# 43-OVER_VOLTAGE_PROTECTION_CKT.net
KiCad netlist of a schematic drawn in Altium Designer
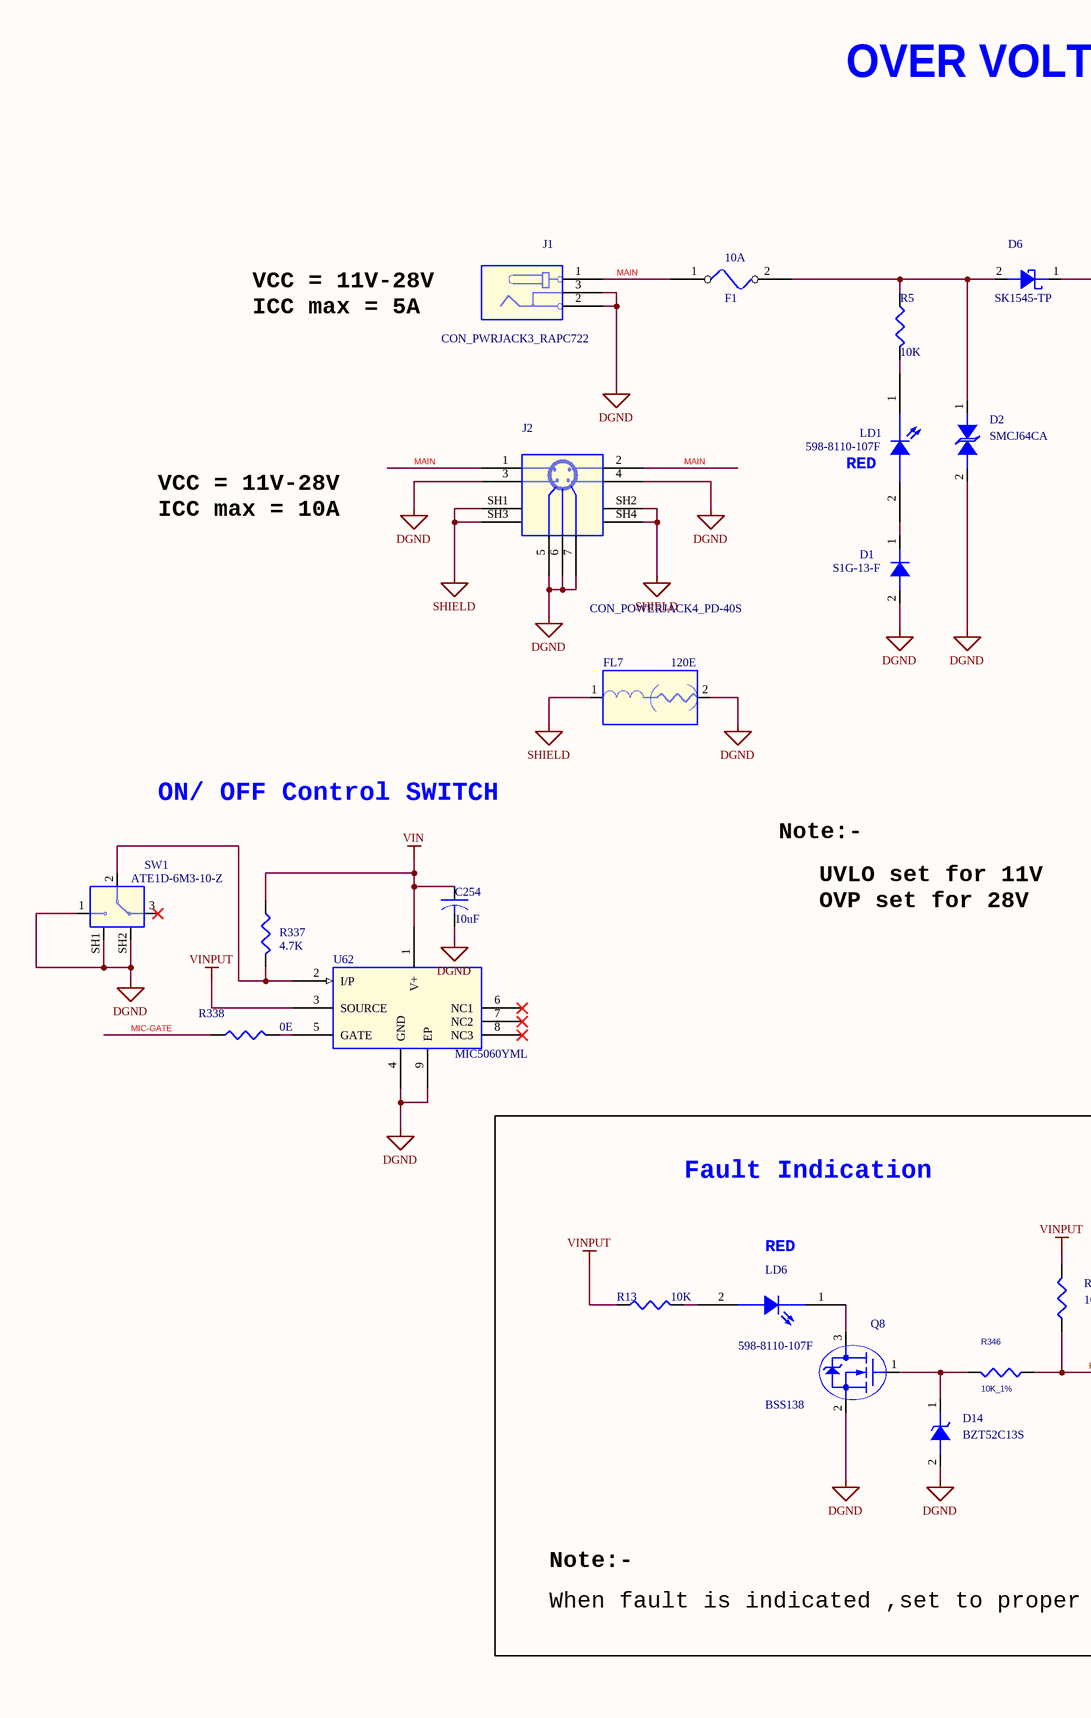
[diagram p0: 43-OVER VOLTAGE PROTECTION CKT.SchDoc, left]
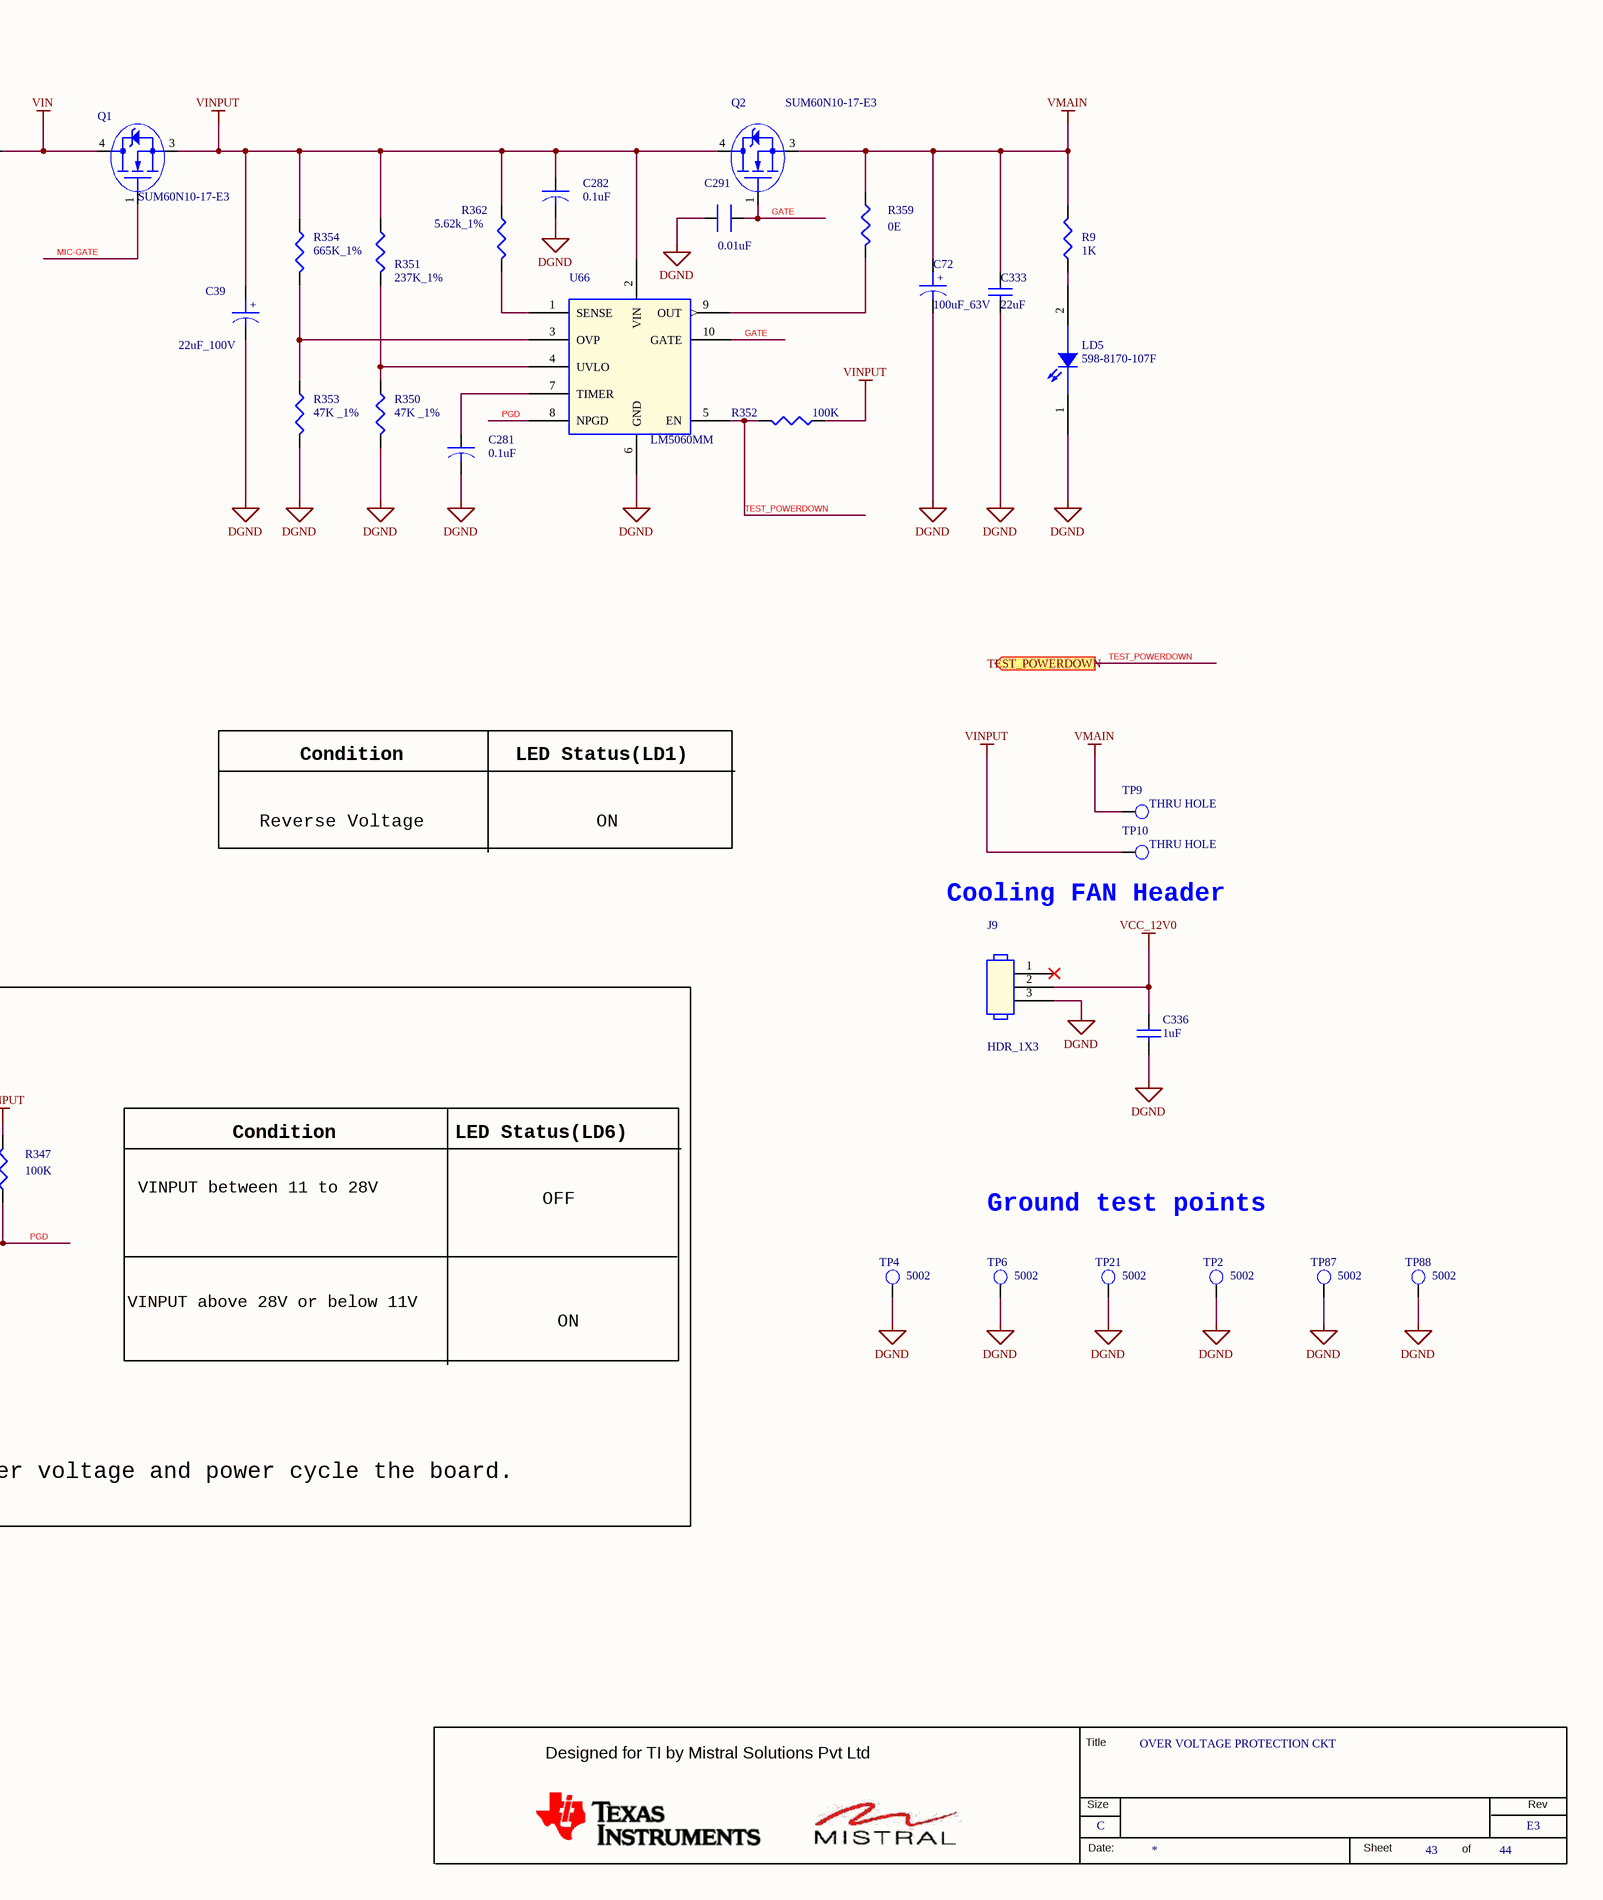
[diagram p1: 43-OVER VOLTAGE PROTECTION CKT.SchDoc, right]

(export (version "E")
  (design (tool "Eeschema 10.0.6"))
  (components
    (comp (ref "C39")
      (value "22uF_100V")
      (footprint "CAPAE_GCASE")
      (description "CAP ELECTROLYTIC 22uF 100V 20% GCASE_103103")
      (fields (field (name "DISTRIBUTOR_PART_NUMBER") "PCE4250CT-ND") (field (name "VOLTAGE") "100V"))
      (libsource (lib "*") (part "CAP_POL"))
    )
    (comp (ref "C72")
      (value "100uF_63V")
      (footprint "CAPAE_CASE103103_11")
      (description "CAP ELECTROLYTIC 100uF 63V 20% CASE_103103")
      (fields
        (field (name "MISTRAL PART NO") "120018010018-R")
        (field (name "MFR_PART_NUMBER") "UUX1J101MNL1GS")
      )
      (libsource (lib "*") (part "CAP_POL"))
    )
    (comp (ref "C254")
      (value "10uF")
      (footprint "CAP1206_2")
      (description "CAP CERAMIC 10uF 50V 20% X5R 1206")
      (fields (field (name "DISTRIBUTOR_PART_NUMBER") "490-10756-1-ND") (field (name "VOLTAGE") "50V"))
      (libsource (lib "*") (part "CAP"))
    )
    (comp (ref "C281")
      (value "0.1uF")
      (footprint "CAP0603_1")
      (description "CAP CERAMIC 0.1uF 50V 20% X7R 0603")
      (fields
        (field (name "MISTRAL PART NO") "120018010021-R")
        (field (name "MFR_PART_NUMBER") "C0603C104M5RACTU")
      )
      (libsource (lib "*") (part "CAP_Dup1"))
    )
    (comp (ref "C282")
      (value "0.1uF")
      (footprint "CAP0603_1")
      (description "CAP CERAMIC 0.1uF 50V 20% X7R 0603")
      (fields
        (field (name "MISTRAL PART NO") "120018010021-R")
        (field (name "MFR_PART_NUMBER") "C0603C104M5RACTU")
      )
      (libsource (lib "*") (part "CAP_Dup1"))
    )
    (comp (ref "C291")
      (value "0.01uF")
      (footprint "TMDX654GPEVM_BRD:CAP0201_0-5")
      (description "CAP CERAMIC 0.01uF 25V 10% X5R 0201")
      (fields
        (field (name "MISTRAL PART NO") "120018010007-R")
        (field (name "MFR_PART_NUMBER") "GRM033R61E103KA12J")
      )
      (libsource (lib "*") (part "CAP_Dup3"))
    )
    (comp (ref "C333")
      (value "22uF")
      (footprint "CAP7563_4")
      (description "CAP CERAMIC 22uF 50V 20% X7R 7563")
      (fields (field (name "DISTRIBUTOR_PART_NUMBER") "565-4700-1-ND") (field (name "VOLTAGE") "50V"))
      (libsource (lib "*") (part "CAP_Dup5"))
    )
    (comp (ref "C336")
      (value "1uF")
      (footprint "CAP0603_1")
      (description "CAP CERAMIC 1uF 25V 10% X5R 0603")
      (fields
        (field (name "MISTRAL PART NO") "120010080040-R")
        (field (name "MFR_PART_NUMBER") "06033D105KAT2A")
      )
      (libsource (lib "*") (part "CAP_Dup5"))
    )
    (comp (ref "D1")
      (value "S1G-13-F")
      (footprint "DIO_SMA")
      (description "DIODE RECTIFIER 400V 1A SMA")
      (fields (field (name "MISTRAL PART NO") "130009030153") (field (name "VOLTAGE") "400V"))
      (libsource (lib "*") (part "DIODE"))
    )
    (comp (ref "D2")
      (value "SMCJ64CA")
      (footprint "DIO_SMC")
      (description "DIODE TVS BI-DIE 1500W 64V SMC")
      (fields (field (name "MISTRAL PART NO") "130015100009-R") (field (name "TOLERANCE") "NA"))
      (libsource (lib "*") (part "DIODE_TVS_DUAL"))
    )
    (comp (ref "D6")
      (value "SK1545-TP")
      (footprint "DO-214AB_5-6")
      (description "DIODE SCHOTTKY RECTIFIER 45V 15A DO-214AB")
      (fields (field (name "MISTRAL PART NO") "130017100014-R") (field (name "TOLERANCE") "NA"))
      (libsource (lib "*") (part "DIODE_SCHOTTKY"))
    )
    (comp (ref "D14")
      (value "BZT52C13S")
      (footprint "DIO_SOD323")
      (description "DIODE ZENER 13V 200mW SOD323")
      (fields
        (field (name "MISTRAL PART NO") "130010120013-R")
        (field (name "MFR_PART_NUMBER") "BZT52C13S-7-F")
      )
      (libsource (lib "*") (part "DIODE_ZENER"))
    )
    (comp (ref "F1")
      (value "10A")
      (footprint "FUSE_397_410X110_SMD_2-9")
      (description "FUSE 10A 60V FAST SMD")
      (fields (field (name "MISTRAL PART NO") "130009030821-R") (field (name "MFR_PART_NUMBER") "1025FA10-R"))
      (libsource (lib "*") (part "FUSE"))
    )
    (comp (ref "FL7")
      (value "120E")
      (footprint "EMIFIL_BLM15A_0402_0-6")
      (description "FERRITE CHIP 120E 1.3A 0402")
      (fields
        (field (name "MISTRAL PART NO") "130012030043-R")
        (field (name "MFR_PART_NUMBER") "BLM15PD121SN1")
      )
      (libsource (lib "*") (part "EMIFILTER_IND"))
    )
    (comp (ref "J1")
      (value "CON_PWRJACK3_RAPC722")
      (footprint "CON_PWRJACK3_RAPC722_P_R_T")
      (description "CON POWER JACK 3POS 5A 1.93MMPIN-DIA MALE RT TH")
      (fields (field (name "DISTRIBUTOR_PART_NUMBER") "SC1313-ND") (field (name "VOLTAGE") "NA"))
      (libsource (lib "*") (part "CON_PWRJACK3_RAPC722"))
    )
    (comp (ref "J2")
      (value "CON_POWERJACK4_PD-40S")
      (footprint "CON_POWERJACK4_PD-40S_S_R_T_15")
      (description "CON POWER JACK 4POS FEMALE RT TH")
      (fields (field (name "MISTRAL PART NO") "150016060015-R") (field (name "MFR_PART_NUMBER") "PD-40S"))
      (libsource (lib "*") (part "CON_POWERJACK_PD-40S"))
    )
    (comp (ref "J9")
      (value "HDR_1X3")
      (footprint "HDR_1X3_440054-3_S_T_6-4")
      (description "CON HDR 1X3 2.00MM PITCH ST TH")
      (fields (field (name "DISTRIBUTOR_PART_NUMBER") "A100035-ND") (field (name "VOLTAGE") "NA"))
      (libsource (lib "*") (part "HEADER_3X1"))
    )
    (comp (ref "LD1")
      (value "598-8110-107F")
      (footprint "LED_0805")
      (description "LED ALINGAP RED CLEAR 0805 SMD")
      (fields (field (name "DISTRIBUTOR_PART_NUMBER") "350-2038-1-ND") (field (name "VOLTAGE") "NA"))
      (libsource (lib "*") (part "LED_598-8170-107F"))
    )
    (comp (ref "LD5")
      (value "598-8170-107F")
      (footprint "LED_0805_0-7")
      (description "LED ALINGAP GREEN CLEAR 0805")
      (fields (field (name "MISTRAL PART NO") "130014050065-R") (field (name "TOLERANCE") "NA"))
      (libsource (lib "*") (part "LED_598-8170-107F"))
    )
    (comp (ref "LD6")
      (value "598-8110-107F")
      (footprint "LED_0805")
      (description "LED ALINGAP RED CLEAR 0805 SMD")
      (fields (field (name "MISTRAL PART NO") "130014050069-R") (field (name "TOLERANCE") "NA"))
      (libsource (lib "*") (part "LED_598-8170-107F"))
    )
    (comp (ref "Q1")
      (value "SUM60N10-17-E3")
      (footprint "D2PAK-3")
      (description "IC POWER MOSFET N-CHANNEL D2PAK")
      (fields (field (name "DISTRIBUTOR_PART_NUMBER") "SUM60N10-17-E3CT-ND") (field (name "VOLTAGE") "100V"))
      (libsource (lib "*") (part "MOSFET_IRFZ24NS"))
    )
    (comp (ref "Q2")
      (value "SUM60N10-17-E3")
      (footprint "D2PAK-3")
      (description "IC POWER MOSFET N-CHANNEL D2PAK")
      (fields (field (name "MISTRAL PART NO") "142015100008-R") (field (name "TOLERANCE") "NA"))
      (libsource (lib "*") (part "MOSFET_IRFZ24NS"))
    )
    (comp (ref "Q8")
      (value "BSS138")
      (footprint "TO_SOT23-123")
      (description "IC MOSFET N-CHANNEL 50V 200mA SOT23-3")
      (fields (field (name "DISTRIBUTOR_PART_NUMBER") "BSS138CT-ND") (field (name "VOLTAGE") "50V"))
      (libsource (lib "*") (part "MOSFET_BSS138"))
    )
    (comp (ref "R5")
      (value "10K")
      (footprint "RES1206")
      (description "RES 10K 2/3W 5% 1206")
      (fields (field (name "DISTRIBUTOR_PART_NUMBER") "P10KALCT-ND") (field (name "VOLTAGE") "NA"))
      (libsource (lib "*") (part "RESISTOR"))
    )
    (comp (ref "R9")
      (value "1K")
      (footprint "TMDX654GPEVM_BRD:RES0201")
      (description "RES 1K 1/20W 5% 0201")
      (fields (field (name "DISTRIBUTOR_PART_NUMBER") "541-1.00KAABCT-ND") (field (name "TOLERANCE") "5%"))
      (libsource (lib "*") (part "RESISTOR_Dup1"))
    )
    (comp (ref "R13")
      (value "10K")
      (footprint "RES1206")
      (description "RES 10K 2/3W 5% 1206")
      (fields
        (field (name "MISTRAL PART NO") "110015090016-R")
        (field (name "MFR_PART_NUMBER") "ERJ-P08J103V")
      )
      (libsource (lib "*") (part "RESISTOR"))
    )
    (comp (ref "R337")
      (value "4.7K")
      (footprint "RES0402")
      (description "RES 4.7K 1/16W 5% 0402")
      (fields (field (name "DISTRIBUTOR_PART_NUMBER") "311-4.7KJRCT-ND") (field (name "VOLTAGE") "NA"))
      (libsource (lib "*") (part "RESISTOR_Dup3"))
    )
    (comp (ref "R338")
      (value "0E")
      (footprint "TMDX654GPEVM_BRD:RES0402_0-5")
      (description "RES 0E 1/16W 0402")
      (fields
        (field (name "MISTRAL PART NO") "110010080019-P")
        (field (name "MFR_PART_NUMBER") "CRCW04020000Z0ED")
      )
      (libsource (lib "*") (part "RESISTOR_Dup2"))
    )
    (comp (ref "R346")
      (value "10K_1%")
      (footprint "RES0402_0-5")
      (description "RES 10K 1/16W 1% 0402")
      (fields (field (name "VOLTAGE") "NA") (field (name "DISTRIBUTOR_PART_NUMBER") "311-10.0KLRTR-ND"))
      (libsource (lib "*") (part "RESISTOR_Dup2"))
    )
    (comp (ref "R347")
      (value "100K")
      (footprint "TMDX654GPEVM_BRD:RES0402_0-5")
      (description "RES 100K 1/16W 5% 0402")
      (fields (field (name "DISTRIBUTOR_PART_NUMBER") "541-100KJCT-ND") (field (name "TOLERANCE") "5%"))
      (libsource (lib "*") (part "RESISTOR_Dup1"))
    )
    (comp (ref "R350")
      (value "47K _1%")
      (footprint "RES0402_0-5")
      (description "RES 47K 1/16W 1% 0402")
      (fields (field (name "VOLTAGE") "NA") (field (name "MISTRAL PART NO") "110009030884-R"))
      (libsource (lib "*") (part "RESISTOR_Dup5"))
    )
    (comp (ref "R351")
      (value "237K_1%")
      (footprint "RES0402")
      (description "RES 237K 1/16W 1% 0402")
      (fields
        (field (name "MISTRAL PART NO") "110015080038-R")
        (field (name "MFR_PART_NUMBER") "RMCF0402FT237K")
      )
      (libsource (lib "*") (part "RESISTOR_Dup5"))
    )
    (comp (ref "R352")
      (value "100K")
      (footprint "TMDX654GPEVM_BRD:RES0402_0-5")
      (description "RES 100K 1/16W 5% 0402")
      (fields (field (name "DISTRIBUTOR_PART_NUMBER") "541-100KJCT-ND") (field (name "TOLERANCE") "5%"))
      (libsource (lib "*") (part "RESISTOR_Dup1"))
    )
    (comp (ref "R353")
      (value "47K _1%")
      (footprint "RES0402_0-5")
      (description "RES 47K 1/16W 1% 0402")
      (fields (field (name "VOLTAGE") "NA") (field (name "DISTRIBUTOR_PART_NUMBER") "311-47.0KLRCT-ND"))
      (libsource (lib "*") (part "RESISTOR_Dup5"))
    )
    (comp (ref "R354")
      (value "665K_1%")
      (footprint "RES0603_0-5")
      (description "RES 665K 1/10W 1% 0603")
      (fields
        (field (name "MISTRAL PART NO") "110017060002-R")
        (field (name "MFR_PART_NUMBER") "CRCW0603665KFKEA")
      )
      (libsource (lib "*") (part "RESISTOR_Dup5"))
    )
    (comp (ref "R359")
      (value "0E")
      (footprint "TMDX654GPEVM_BRD:RES0402_0-5")
      (description "RES 0E 1/16W 0402")
      (fields (field (name "VOLTAGE") "NA") (field (name "DISTRIBUTOR_PART_NUMBER") "541-0.0JCT-ND"))
      (libsource (lib "*") (part "RESISTOR_Dup2"))
    )
    (comp (ref "R362")
      (value "5.62k_1%")
      (footprint "RES0603")
      (description "RES 5.62K 1/10W 1% 0603")
      (fields (field (name "DISTRIBUTOR_PART_NUMBER") "541-5.62KHCT-ND") (field (name "VOLTAGE") "NA"))
      (libsource (lib "*") (part "RESISTOR_Dup5"))
    )
    (comp (ref "SW1")
      (value "ATE1D-6M3-10-Z")
      (footprint "SW3_ATE1F-6M3_370X710_TH_5-6")
      (description "SWITCH TOGGLE SPDT RT TH")
      (fields (field (name "MISTRAL PART NO") "130017120017-R") (field (name "TOLERANCE") "NA"))
      (libsource (lib "*") (part "SW3_B12JV"))
    )
    (comp (ref "TP2")
      (value "5002")
      (footprint "TP_CIR67D40_TH_4-6")
      (description "ACCESSORIE PC TEST POINT")
      (fields (field (name "MISTRAL PART NO") "160016120008-R") (field (name "TOLERANCE") "NA"))
      (libsource (lib "*") (part "TESTPOINT"))
    )
    (comp (ref "TP4")
      (value "5002")
      (footprint "TP_CIR67D40_TH_4-6")
      (description "ACCESSORIE PC TEST POINT")
      (fields (field (name "MISTRAL PART NO") "160016120008-R") (field (name "TOLERANCE") "NA"))
      (libsource (lib "*") (part "TESTPOINT"))
    )
    (comp (ref "TP6")
      (value "5002")
      (footprint "TP_CIR67D40_TH_4-6")
      (description "ACCESSORIE PC TEST POINT")
      (fields (field (name "MISTRAL PART NO") "160016120008-R") (field (name "TOLERANCE") "NA"))
      (libsource (lib "*") (part "TESTPOINT"))
    )
    (comp (ref "TP9")
      (value "THRU HOLE")
      (footprint "TP_40X65")
      (description "TESTPOINT 1.0MM DRILL PTH")
      (fields (field (name "DISTRIBUTOR_PART_NUMBER") "NA") (field (name "MFR_PART_NUMBER") "TP_40X65"))
      (libsource (lib "*") (part "TESTPOINT"))
    )
    (comp (ref "TP10")
      (value "THRU HOLE")
      (footprint "TP_40X65")
      (description "TESTPOINT 1.0MM DRILL PTH")
      (fields (field (name "MISTRAL PART NO") "130009030938") (field (name "MFR_PART_NUMBER") "TP_40X65"))
      (libsource (lib "*") (part "TESTPOINT"))
    )
    (comp (ref "TP21")
      (value "5002")
      (footprint "TP_CIR67D40_TH_4-6")
      (description "ACCESSORIE PC TEST POINT")
      (fields (field (name "MISTRAL PART NO") "160016120008-R") (field (name "TOLERANCE") "NA"))
      (libsource (lib "*") (part "TESTPOINT"))
    )
    (comp (ref "TP87")
      (value "5002")
      (footprint "TP_CIR67D40_TH_4-6")
      (description "ACCESSORIE PC TEST POINT")
      (fields (field (name "DISTRIBUTOR_PART_NUMBER") "36-5002-ND") (field (name "VOLTAGE") "NA"))
      (libsource (lib "*") (part "TESTPOINT"))
    )
    (comp (ref "TP88")
      (value "5002")
      (footprint "TP_CIR67D40_TH_4-6")
      (description "ACCESSORIE PC TEST POINT")
      (fields (field (name "MISTRAL PART NO") "160016120008-R") (field (name "TOLERANCE") "NA"))
      (libsource (lib "*") (part "TESTPOINT"))
    )
    (comp (ref "U62")
      (value "MIC5060YML")
      (footprint "DFN8_25-59_120X120_1")
      (description "IC ULTRA SMALL HIGH SIDE MOSFET DRIVER MLF8")
      (fields
        (field (name "MISTRAL PART NO") "142017100011-R")
        (field (name "MFR_PART_NUMBER") "MIC5060YML-TR")
      )
      (libsource (lib "*") (part "MIC5060YML_MLF8"))
    )
    (comp (ref "U66")
      (value "LM5060MM")
      (footprint "MSOP10_19-68_120X120")
      (description "IC CONTROLLER HIGH-SIDE PROTECTION VSSOP10")
      (fields (field (name "DISTRIBUTOR_PART_NUMBER") "296-39024-1-ND") (field (name "VOLTAGE") "NA"))
      (libsource (lib "*") (part "LM5060_MSOP10"))
    )
  )
  (nets
    (net (code "1") (name "/GATE") (class "Default")
      (node (ref "C291") (pin "1") (pinfunction "1_1") (pintype "passive"))
      (node (ref "Q2") (pin "1") (pinfunction "G_1") (pintype "passive"))
      (node (ref "U66") (pin "10") (pinfunction "GATE_10") (pintype "passive"))
    )
    (net (code "2") (name "/MAIN") (class "Default")
      (node (ref "F1") (pin "1") (pinfunction "1_1") (pintype "passive"))
      (node (ref "J1") (pin "1") (pinfunction "1_1") (pintype "passive"))
      (node (ref "J2") (pin "1") (pinfunction "1_1") (pintype "passive"))
      (node (ref "J2") (pin "2") (pinfunction "2_2") (pintype "passive"))
    )
    (net (code "3") (name "/MIC-GATE") (class "Default")
      (node (ref "Q1") (pin "1") (pinfunction "G_1") (pintype "passive"))
      (node (ref "R338") (pin "1") (pinfunction "1_1") (pintype "passive"))
    )
    (net (code "4") (name "/PGD") (class "Default")
      (node (ref "R346") (pin "1") (pinfunction "1_1") (pintype "passive"))
      (node (ref "R347") (pin "1") (pinfunction "1_1") (pintype "passive"))
      (node (ref "U66") (pin "8") (pinfunction "NPGD_8") (pintype "passive"))
    )
    (net (code "5") (name "/TEST_POWERDOWN") (class "Default")
      (node (ref "R352") (pin "2") (pinfunction "2_2") (pintype "passive"))
      (node (ref "U66") (pin "5") (pinfunction "EN_5") (pintype "passive"))
    )
    (net (code "6") (name "DGND") (class "Default")
      (node (ref "C254") (pin "2") (pinfunction "2_2") (pintype "passive"))
      (node (ref "C281") (pin "2") (pinfunction "2_2") (pintype "passive"))
      (node (ref "C282") (pin "2") (pinfunction "2_2") (pintype "passive"))
      (node (ref "C291") (pin "2") (pinfunction "2_2") (pintype "passive"))
      (node (ref "C333") (pin "2") (pinfunction "2_2") (pintype "passive"))
      (node (ref "C336") (pin "2") (pinfunction "2_2") (pintype "passive"))
      (node (ref "C39") (pin "2") (pinfunction "2_2") (pintype "passive"))
      (node (ref "C72") (pin "2") (pinfunction "2_2") (pintype "passive"))
      (node (ref "D1") (pin "2") (pinfunction "A_2") (pintype "passive"))
      (node (ref "D14") (pin "2") (pinfunction "ANODE_2") (pintype "passive"))
      (node (ref "D2") (pin "2") (pinfunction "ANODE_2") (pintype "passive"))
      (node (ref "FL7") (pin "2") (pinfunction "2_2") (pintype "passive"))
      (node (ref "J1") (pin "2") (pinfunction "2_2") (pintype "passive"))
      (node (ref "J1") (pin "3") (pinfunction "3_3") (pintype "passive"))
      (node (ref "J2") (pin "3") (pinfunction "3_3") (pintype "passive"))
      (node (ref "J2") (pin "4") (pinfunction "4_4") (pintype "passive"))
      (node (ref "J2") (pin "5") (pinfunction "5_5") (pintype "passive"))
      (node (ref "J2") (pin "6") (pinfunction "6_6") (pintype "passive"))
      (node (ref "J2") (pin "7") (pinfunction "7_7") (pintype "passive"))
      (node (ref "J9") (pin "3") (pinfunction "3_3") (pintype "passive"))
      (node (ref "LD5") (pin "1") (pinfunction "1_1") (pintype "passive"))
      (node (ref "Q8") (pin "2") (pinfunction "S_2") (pintype "passive"))
      (node (ref "R350") (pin "2") (pinfunction "2_2") (pintype "passive"))
      (node (ref "R353") (pin "2") (pinfunction "2_2") (pintype "passive"))
      (node (ref "SW1") (pin "1") (pinfunction "1_1") (pintype "passive"))
      (node (ref "SW1") (pin "SH1") (pinfunction "SH1_SH1") (pintype "passive"))
      (node (ref "SW1") (pin "SH2") (pinfunction "SH2_SH2") (pintype "passive"))
      (node (ref "TP2") (pin "1") (pinfunction "TP_1") (pintype "passive"))
      (node (ref "TP21") (pin "1") (pinfunction "TP_1") (pintype "passive"))
      (node (ref "TP4") (pin "1") (pinfunction "TP_1") (pintype "passive"))
      (node (ref "TP6") (pin "1") (pinfunction "TP_1") (pintype "passive"))
      (node (ref "TP87") (pin "1") (pinfunction "TP_1") (pintype "passive"))
      (node (ref "TP88") (pin "1") (pinfunction "TP_1") (pintype "passive"))
      (node (ref "U62") (pin "4") (pinfunction "GND_4") (pintype "power_in"))
      (node (ref "U62") (pin "9") (pinfunction "EP_9") (pintype "power_in"))
      (node (ref "U66") (pin "6") (pinfunction "GND_6") (pintype "power_in"))
    )
    (net (code "7") (name "Net-(D1-K)") (class "Default")
      (node (ref "D1") (pin "1") (pinfunction "K_1") (pintype "passive"))
      (node (ref "LD1") (pin "2") (pinfunction "2_2") (pintype "passive"))
    )
    (net (code "8") (name "Net-(D2-CATHODE)") (class "Default")
      (node (ref "D2") (pin "1") (pinfunction "CATHODE_1") (pintype "passive"))
      (node (ref "D6") (pin "2") (pinfunction "ANODE_2") (pintype "passive"))
      (node (ref "F1") (pin "2") (pinfunction "2_2") (pintype "passive"))
      (node (ref "R5") (pin "1") (pinfunction "1_1") (pintype "passive"))
    )
    (net (code "9") (name "Net-(D14-CATHODE)") (class "Default")
      (node (ref "D14") (pin "1") (pinfunction "CATHODE_1") (pintype "passive"))
      (node (ref "Q8") (pin "1") (pinfunction "G_1") (pintype "passive"))
      (node (ref "R346") (pin "2") (pinfunction "2_2") (pintype "passive"))
    )
    (net (code "10") (name "Net-(LD1-Pad1)") (class "Default")
      (node (ref "LD1") (pin "1") (pinfunction "1_1") (pintype "passive"))
      (node (ref "R5") (pin "2") (pinfunction "2_2") (pintype "passive"))
    )
    (net (code "11") (name "Net-(LD5-Pad2)") (class "Default")
      (node (ref "LD5") (pin "2") (pinfunction "2_2") (pintype "passive"))
      (node (ref "R9") (pin "2") (pinfunction "2_2") (pintype "passive"))
    )
    (net (code "12") (name "Net-(LD6-Pad2)") (class "Default")
      (node (ref "LD6") (pin "2") (pinfunction "2_2") (pintype "passive"))
      (node (ref "R13") (pin "2") (pinfunction "2_2") (pintype "passive"))
    )
    (net (code "13") (name "Net-(Q8-D)") (class "Default")
      (node (ref "LD6") (pin "1") (pinfunction "1_1") (pintype "passive"))
      (node (ref "Q8") (pin "3") (pinfunction "D_3") (pintype "passive"))
    )
    (net (code "14") (name "Net-(U62-GATE)") (class "Default")
      (node (ref "R338") (pin "2") (pinfunction "2_2") (pintype "passive"))
      (node (ref "U62") (pin "5") (pinfunction "GATE_5") (pintype "passive"))
    )
    (net (code "15") (name "Net-(U62-I{slash}P)") (class "Default")
      (node (ref "R337") (pin "2") (pinfunction "2_2") (pintype "passive"))
      (node (ref "SW1") (pin "2") (pinfunction "2_2") (pintype "passive"))
      (node (ref "U62") (pin "2") (pinfunction "I/P_2") (pintype "input"))
    )
    (net (code "16") (name "Net-(U66-OUT)") (class "Default")
      (node (ref "R359") (pin "2") (pinfunction "2_2") (pintype "passive"))
      (node (ref "U66") (pin "9") (pinfunction "OUT_9") (pintype "output"))
    )
    (net (code "17") (name "Net-(U66-OVP)") (class "Default")
      (node (ref "R353") (pin "1") (pinfunction "1_1") (pintype "passive"))
      (node (ref "R354") (pin "2") (pinfunction "2_2") (pintype "passive"))
      (node (ref "U66") (pin "3") (pinfunction "OVP_3") (pintype "passive"))
    )
    (net (code "18") (name "Net-(U66-SENSE)") (class "Default")
      (node (ref "R362") (pin "2") (pinfunction "2_2") (pintype "passive"))
      (node (ref "U66") (pin "1") (pinfunction "SENSE_1") (pintype "passive"))
    )
    (net (code "19") (name "Net-(U66-TIMER)") (class "Default")
      (node (ref "C281") (pin "1") (pinfunction "1_1") (pintype "passive"))
      (node (ref "U66") (pin "7") (pinfunction "TIMER_7") (pintype "passive"))
    )
    (net (code "20") (name "Net-(U66-UVLO)") (class "Default")
      (node (ref "R350") (pin "1") (pinfunction "1_1") (pintype "passive"))
      (node (ref "R351") (pin "2") (pinfunction "2_2") (pintype "passive"))
      (node (ref "U66") (pin "4") (pinfunction "UVLO_4") (pintype "passive"))
    )
    (net (code "21") (name "SHIELD") (class "Default")
      (node (ref "FL7") (pin "1") (pinfunction "1_1") (pintype "passive"))
      (node (ref "J2") (pin "SH1") (pinfunction "SH1_SH1") (pintype "passive"))
      (node (ref "J2") (pin "SH2") (pinfunction "SH2_SH2") (pintype "passive"))
      (node (ref "J2") (pin "SH3") (pinfunction "SH3_SH3") (pintype "passive"))
      (node (ref "J2") (pin "SH4") (pinfunction "SH4_SH4") (pintype "passive"))
    )
    (net (code "22") (name "VCC_12V0") (class "Default")
      (node (ref "C336") (pin "1") (pinfunction "1_1") (pintype "passive"))
      (node (ref "J9") (pin "2") (pinfunction "2_2") (pintype "passive"))
    )
    (net (code "23") (name "VIN") (class "Default")
      (node (ref "C254") (pin "1") (pinfunction "1_1") (pintype "passive"))
      (node (ref "D6") (pin "1") (pinfunction "CATHODE_1") (pintype "passive"))
      (node (ref "Q1") (pin "4") (pinfunction "D_4") (pintype "passive"))
      (node (ref "R337") (pin "1") (pinfunction "1_1") (pintype "passive"))
      (node (ref "U62") (pin "1") (pinfunction "V+_1") (pintype "power_in"))
    )
    (net (code "24") (name "VINPUT") (class "Default")
      (node (ref "C282") (pin "1") (pinfunction "1_1") (pintype "passive"))
      (node (ref "C39") (pin "1") (pinfunction "1_1") (pintype "passive"))
      (node (ref "Q1") (pin "3") (pinfunction "S_3") (pintype "passive"))
      (node (ref "Q2") (pin "4") (pinfunction "D_4") (pintype "passive"))
      (node (ref "R13") (pin "1") (pinfunction "1_1") (pintype "passive"))
      (node (ref "R347") (pin "2") (pinfunction "2_2") (pintype "passive"))
      (node (ref "R351") (pin "1") (pinfunction "1_1") (pintype "passive"))
      (node (ref "R352") (pin "1") (pinfunction "1_1") (pintype "passive"))
      (node (ref "R354") (pin "1") (pinfunction "1_1") (pintype "passive"))
      (node (ref "R362") (pin "1") (pinfunction "1_1") (pintype "passive"))
      (node (ref "TP10") (pin "1") (pinfunction "TP_1") (pintype "passive"))
      (node (ref "U62") (pin "3") (pinfunction "SOURCE_3") (pintype "passive"))
      (node (ref "U66") (pin "2") (pinfunction "VIN_2") (pintype "power_in"))
    )
    (net (code "25") (name "VMAIN") (class "Default")
      (node (ref "C333") (pin "1") (pinfunction "1_1") (pintype "passive"))
      (node (ref "C72") (pin "1") (pinfunction "1_1") (pintype "passive"))
      (node (ref "Q2") (pin "3") (pinfunction "S_3") (pintype "passive"))
      (node (ref "R359") (pin "1") (pinfunction "1_1") (pintype "passive"))
      (node (ref "R9") (pin "1") (pinfunction "1_1") (pintype "passive"))
      (node (ref "TP9") (pin "1") (pinfunction "TP_1") (pintype "passive"))
    )
    (net (code "26") (name "unconnected-(J9-Pad1)") (class "Default")
      (node (ref "J9") (pin "1") (pinfunction "1_1") (pintype "passive+no_connect"))
    )
    (net (code "27") (name "unconnected-(SW1-Pad3)") (class "Default")
      (node (ref "SW1") (pin "3") (pinfunction "3_3") (pintype "passive+no_connect"))
    )
    (net (code "28") (name "unconnected-(U62-NC1-Pad6)") (class "Default")
      (node (ref "U62") (pin "6") (pinfunction "NC1_6") (pintype "passive+no_connect"))
    )
    (net (code "29") (name "unconnected-(U62-NC2-Pad7)") (class "Default")
      (node (ref "U62") (pin "7") (pinfunction "NC2_7") (pintype "passive+no_connect"))
    )
    (net (code "30") (name "unconnected-(U62-NC3-Pad8)") (class "Default")
      (node (ref "U62") (pin "8") (pinfunction "NC3_8") (pintype "passive+no_connect"))
    )
  )
)
